# Power.net
KiCad netlist of a schematic drawn in Altium Designer
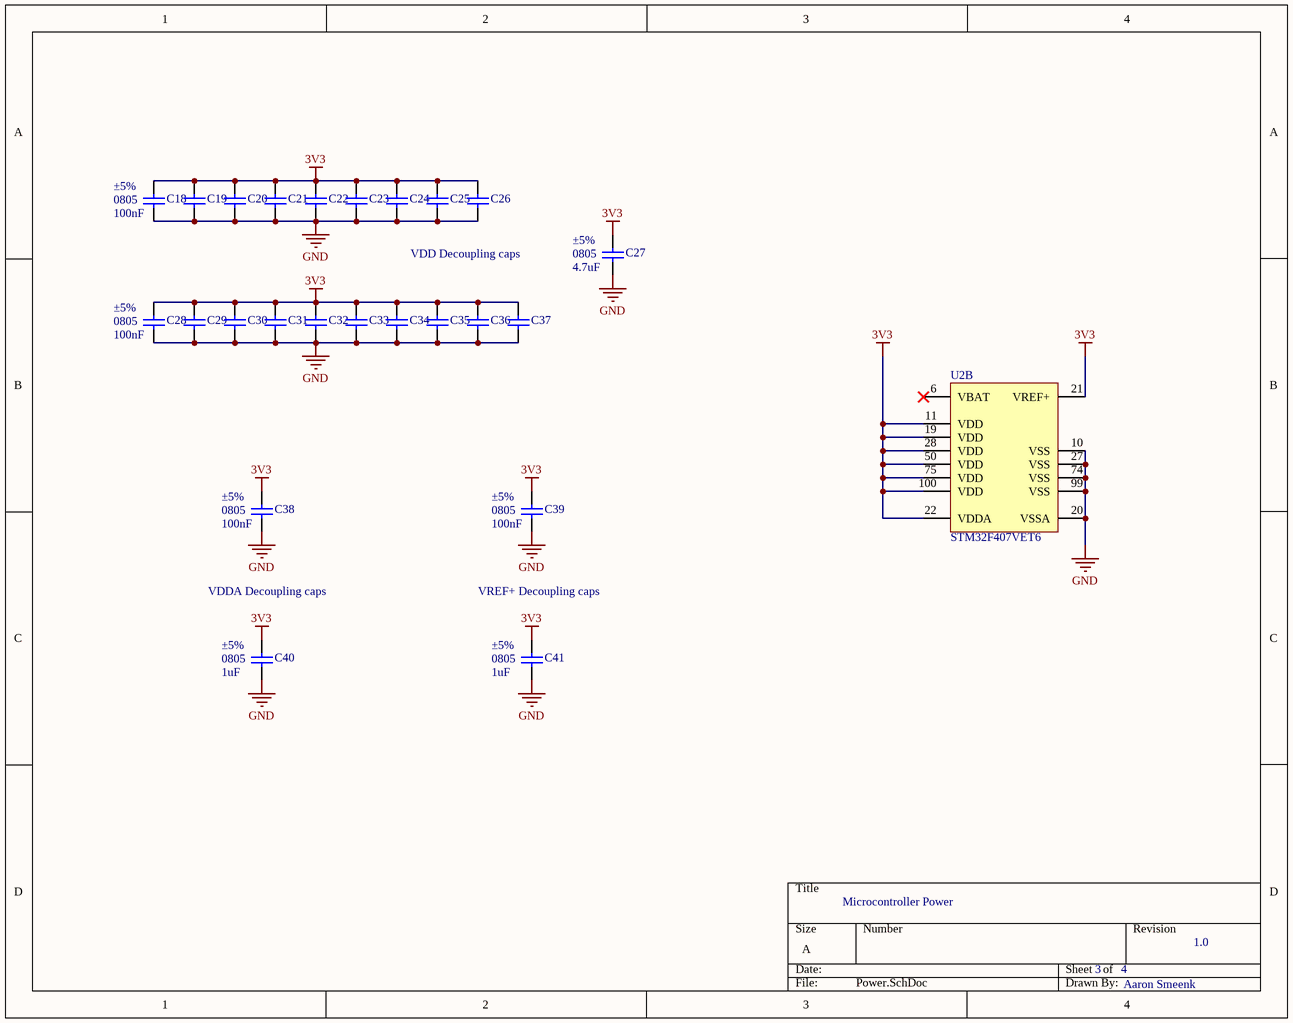
[diagram p0: Power.SchDoc]

(export (version "E")
  (design (tool "Eeschema 10.0.6"))
  (components
    (comp (ref "C18")
      (value "100nF")
      (footprint "CAPC0805(2012)100_M")
      (description "CAP 100nF 6.3V ±5% 0805 (2012 Metric) Thickness 1mm SMD")
      (fields
        (field (name "TOLERANCE") "±5%")
        (field (name "CASE-EIA") "0805")
        (field (name "Comment") "CAP 100nF 6.3V 0805(2012)")
      )
      (libsource (lib "Altium Content Vault") (part "CMP-1036-04390-1"))
    )
    (comp (ref "C19")
      (value "CAP 100nF 6.3V 0805(2012)")
      (footprint "CAPC0805(2012)100_M")
      (description "CAP 100nF 6.3V ±5% 0805 (2012 Metric) Thickness 1mm SMD")
      (fields (field (name "TOLERANCE") "±5%"))
      (libsource (lib "Altium Content Vault") (part "CMP-1036-04390-1"))
    )
    (comp (ref "C20")
      (value "CAP 100nF 6.3V 0805(2012)")
      (footprint "CAPC0805(2012)100_M")
      (description "CAP 100nF 6.3V ±5% 0805 (2012 Metric) Thickness 1mm SMD")
      (fields (field (name "TOLERANCE") "±5%"))
      (libsource (lib "Altium Content Vault") (part "CMP-1036-04390-1"))
    )
    (comp (ref "C21")
      (value "CAP 100nF 6.3V 0805(2012)")
      (footprint "CAPC0805(2012)100_M")
      (description "CAP 100nF 6.3V ±5% 0805 (2012 Metric) Thickness 1mm SMD")
      (fields (field (name "TOLERANCE") "±5%"))
      (libsource (lib "Altium Content Vault") (part "CMP-1036-04390-1"))
    )
    (comp (ref "C22")
      (value "CAP 100nF 6.3V 0805(2012)")
      (footprint "CAPC0805(2012)100_M")
      (description "CAP 100nF 6.3V ±5% 0805 (2012 Metric) Thickness 1mm SMD")
      (fields (field (name "TOLERANCE") "±5%"))
      (libsource (lib "Altium Content Vault") (part "CMP-1036-04390-1"))
    )
    (comp (ref "C23")
      (value "CAP 100nF 6.3V 0805(2012)")
      (footprint "CAPC0805(2012)100_M")
      (description "CAP 100nF 6.3V ±5% 0805 (2012 Metric) Thickness 1mm SMD")
      (fields (field (name "TOLERANCE") "±5%"))
      (libsource (lib "Altium Content Vault") (part "CMP-1036-04390-1"))
    )
    (comp (ref "C24")
      (value "CAP 100nF 6.3V 0805(2012)")
      (footprint "CAPC0805(2012)100_M")
      (description "CAP 100nF 6.3V ±5% 0805 (2012 Metric) Thickness 1mm SMD")
      (fields (field (name "TOLERANCE") "±5%"))
      (libsource (lib "Altium Content Vault") (part "CMP-1036-04390-1"))
    )
    (comp (ref "C25")
      (value "CAP 100nF 6.3V 0805(2012)")
      (footprint "CAPC0805(2012)100_M")
      (description "CAP 100nF 6.3V ±5% 0805 (2012 Metric) Thickness 1mm SMD")
      (fields (field (name "TOLERANCE") "±5%"))
      (libsource (lib "Altium Content Vault") (part "CMP-1036-04390-1"))
    )
    (comp (ref "C26")
      (value "CAP 100nF 6.3V 0805(2012)")
      (footprint "CAPC0805(2012)100_M")
      (description "CAP 100nF 6.3V ±5% 0805 (2012 Metric) Thickness 1mm SMD")
      (fields (field (name "TOLERANCE") "±5%"))
      (libsource (lib "Altium Content Vault") (part "CMP-1036-04390-1"))
    )
    (comp (ref "C27")
      (value "4.7uF")
      (footprint "CAPC0805(2012)145_L")
      (description "CAP 4.7uF 6.3V ±5% 0805 (2012 Metric) Thickness 1.45mm SMD")
      (fields
        (field (name "CASE-EIA") "0805")
        (field (name "TOLERANCE") "±5%")
        (field (name "Comment") "CAP 4.7uF 6.3V 0805(2012)")
      )
      (libsource (lib "Altium Content Vault") (part "CMP-1036-04781-1"))
    )
    (comp (ref "C28")
      (value "100nF")
      (footprint "CAPC0805(2012)100_M")
      (description "CAP 100nF 6.3V ±5% 0805 (2012 Metric) Thickness 1mm SMD")
      (fields
        (field (name "TOLERANCE") "±5%")
        (field (name "CASE-EIA") "0805")
        (field (name "Comment") "CAP 100nF 6.3V 0805(2012)")
      )
      (libsource (lib "Altium Content Vault") (part "CMP-1036-04390-1"))
    )
    (comp (ref "C29")
      (value "CAP 100nF 6.3V 0805(2012)")
      (footprint "CAPC0805(2012)100_M")
      (description "CAP 100nF 6.3V ±5% 0805 (2012 Metric) Thickness 1mm SMD")
      (fields (field (name "TOLERANCE") "±5%"))
      (libsource (lib "Altium Content Vault") (part "CMP-1036-04390-1"))
    )
    (comp (ref "C30")
      (value "CAP 100nF 6.3V 0805(2012)")
      (footprint "CAPC0805(2012)100_M")
      (description "CAP 100nF 6.3V ±5% 0805 (2012 Metric) Thickness 1mm SMD")
      (fields (field (name "TOLERANCE") "±5%"))
      (libsource (lib "Altium Content Vault") (part "CMP-1036-04390-1"))
    )
    (comp (ref "C31")
      (value "CAP 100nF 6.3V 0805(2012)")
      (footprint "CAPC0805(2012)100_M")
      (description "CAP 100nF 6.3V ±5% 0805 (2012 Metric) Thickness 1mm SMD")
      (fields (field (name "TOLERANCE") "±5%"))
      (libsource (lib "Altium Content Vault") (part "CMP-1036-04390-1"))
    )
    (comp (ref "C32")
      (value "CAP 100nF 6.3V 0805(2012)")
      (footprint "CAPC0805(2012)100_M")
      (description "CAP 100nF 6.3V ±5% 0805 (2012 Metric) Thickness 1mm SMD")
      (fields (field (name "TOLERANCE") "±5%"))
      (libsource (lib "Altium Content Vault") (part "CMP-1036-04390-1"))
    )
    (comp (ref "C33")
      (value "CAP 100nF 6.3V 0805(2012)")
      (footprint "CAPC0805(2012)100_M")
      (description "CAP 100nF 6.3V ±5% 0805 (2012 Metric) Thickness 1mm SMD")
      (fields (field (name "TOLERANCE") "±5%"))
      (libsource (lib "Altium Content Vault") (part "CMP-1036-04390-1"))
    )
    (comp (ref "C34")
      (value "CAP 100nF 6.3V 0805(2012)")
      (footprint "CAPC0805(2012)100_M")
      (description "CAP 100nF 6.3V ±5% 0805 (2012 Metric) Thickness 1mm SMD")
      (fields (field (name "TOLERANCE") "±5%"))
      (libsource (lib "Altium Content Vault") (part "CMP-1036-04390-1"))
    )
    (comp (ref "C35")
      (value "CAP 100nF 6.3V 0805(2012)")
      (footprint "CAPC0805(2012)100_M")
      (description "CAP 100nF 6.3V ±5% 0805 (2012 Metric) Thickness 1mm SMD")
      (fields (field (name "TOLERANCE") "±5%"))
      (libsource (lib "Altium Content Vault") (part "CMP-1036-04390-1"))
    )
    (comp (ref "C36")
      (value "CAP 100nF 6.3V 0805(2012)")
      (footprint "CAPC0805(2012)100_M")
      (description "CAP 100nF 6.3V ±5% 0805 (2012 Metric) Thickness 1mm SMD")
      (fields (field (name "TOLERANCE") "±5%"))
      (libsource (lib "Altium Content Vault") (part "CMP-1036-04390-1"))
    )
    (comp (ref "C37")
      (value "CAP 100nF 6.3V 0805(2012)")
      (footprint "CAPC0805(2012)100_M")
      (description "CAP 100nF 6.3V ±5% 0805 (2012 Metric) Thickness 1mm SMD")
      (fields (field (name "TOLERANCE") "±5%"))
      (libsource (lib "Altium Content Vault") (part "CMP-1036-04390-1"))
    )
    (comp (ref "C38")
      (value "100nF")
      (footprint "CAPC0805(2012)100_M")
      (description "CAP 100nF 6.3V ±5% 0805 (2012 Metric) Thickness 1mm SMD")
      (fields
        (field (name "TOLERANCE") "±5%")
        (field (name "CASE-EIA") "0805")
        (field (name "Comment") "CAP 100nF 6.3V 0805(2012)")
      )
      (libsource (lib "Altium Content Vault") (part "CMP-1036-04390-1"))
    )
    (comp (ref "C39")
      (value "100nF")
      (footprint "CAPC0805(2012)100_M")
      (description "CAP 100nF 6.3V ±5% 0805 (2012 Metric) Thickness 1mm SMD")
      (fields
        (field (name "TOLERANCE") "±5%")
        (field (name "CASE-EIA") "0805")
        (field (name "Comment") "CAP 100nF 6.3V 0805(2012)")
      )
      (libsource (lib "Altium Content Vault") (part "CMP-1036-04390-1"))
    )
    (comp (ref "C40")
      (value "1uF")
      (footprint "CAPC0805(2012)145_L")
      (description "CAP 1uF 6.3V ±5% 0805 (2012 Metric) Thickness 1.45mm SMD")
      (fields
        (field (name "CASE-EIA") "0805")
        (field (name "TOLERANCE") "±5%")
        (field (name "Comment") "CAP 1uF 6.3V 0805(2012)")
      )
      (libsource (lib "Altium Content Vault") (part "CMP-1036-04781-1"))
    )
    (comp (ref "C41")
      (value "1uF")
      (footprint "CAPC0805(2012)145_L")
      (description "CAP 1uF 6.3V ±5% 0805 (2012 Metric) Thickness 1.45mm SMD")
      (fields
        (field (name "CASE-EIA") "0805")
        (field (name "TOLERANCE") "±5%")
        (field (name "Comment") "CAP 1uF 6.3V 0805(2012)")
      )
      (libsource (lib "Altium Content Vault") (part "CMP-1036-04781-1"))
    )
    (comp (ref "U2")
      (value "STM32F407VET6")
      (footprint "STM-LQFP100_M")
      (fields (field (name "MANUFACTURER") "STMicroelectronics"))
      (libsource (lib "Altium Content Vault") (part "MC-ARM-STM32F40X_41X-SQ100"))
    )
  )
  (nets
    (net (code "1") (name "3V3") (class "Default")
      (node (ref "C18") (pin "2") (pinfunction "2_2") (pintype "passive"))
      (node (ref "C19") (pin "2") (pinfunction "2_2") (pintype "passive"))
      (node (ref "C20") (pin "2") (pinfunction "2_2") (pintype "passive"))
      (node (ref "C21") (pin "2") (pinfunction "2_2") (pintype "passive"))
      (node (ref "C22") (pin "2") (pinfunction "2_2") (pintype "passive"))
      (node (ref "C23") (pin "2") (pinfunction "2_2") (pintype "passive"))
      (node (ref "C24") (pin "2") (pinfunction "2_2") (pintype "passive"))
      (node (ref "C25") (pin "2") (pinfunction "2_2") (pintype "passive"))
      (node (ref "C26") (pin "2") (pinfunction "2_2") (pintype "passive"))
      (node (ref "C27") (pin "2") (pinfunction "2_2") (pintype "passive"))
      (node (ref "C28") (pin "2") (pinfunction "2_2") (pintype "passive"))
      (node (ref "C29") (pin "2") (pinfunction "2_2") (pintype "passive"))
      (node (ref "C30") (pin "2") (pinfunction "2_2") (pintype "passive"))
      (node (ref "C31") (pin "2") (pinfunction "2_2") (pintype "passive"))
      (node (ref "C32") (pin "2") (pinfunction "2_2") (pintype "passive"))
      (node (ref "C33") (pin "2") (pinfunction "2_2") (pintype "passive"))
      (node (ref "C34") (pin "2") (pinfunction "2_2") (pintype "passive"))
      (node (ref "C35") (pin "2") (pinfunction "2_2") (pintype "passive"))
      (node (ref "C36") (pin "2") (pinfunction "2_2") (pintype "passive"))
      (node (ref "C37") (pin "2") (pinfunction "2_2") (pintype "passive"))
      (node (ref "C38") (pin "2") (pinfunction "2_2") (pintype "passive"))
      (node (ref "C39") (pin "2") (pinfunction "2_2") (pintype "passive"))
      (node (ref "C40") (pin "2") (pinfunction "2_2") (pintype "passive"))
      (node (ref "C41") (pin "2") (pinfunction "2_2") (pintype "passive"))
      (node (ref "U2") (pin "100") (pinfunction "VDD_100") (pintype "power_in"))
      (node (ref "U2") (pin "11") (pinfunction "VDD_11") (pintype "power_in"))
      (node (ref "U2") (pin "19") (pinfunction "VDD_19") (pintype "power_in"))
      (node (ref "U2") (pin "21") (pinfunction "VREF+_21") (pintype "power_in"))
      (node (ref "U2") (pin "22") (pinfunction "VDDA_22") (pintype "power_in"))
      (node (ref "U2") (pin "28") (pinfunction "VDD_28") (pintype "power_in"))
      (node (ref "U2") (pin "50") (pinfunction "VDD_50") (pintype "power_in"))
      (node (ref "U2") (pin "75") (pinfunction "VDD_75") (pintype "power_in"))
    )
    (net (code "2") (name "GND") (class "Default")
      (node (ref "C18") (pin "1") (pinfunction "1_1") (pintype "passive"))
      (node (ref "C19") (pin "1") (pinfunction "1_1") (pintype "passive"))
      (node (ref "C20") (pin "1") (pinfunction "1_1") (pintype "passive"))
      (node (ref "C21") (pin "1") (pinfunction "1_1") (pintype "passive"))
      (node (ref "C22") (pin "1") (pinfunction "1_1") (pintype "passive"))
      (node (ref "C23") (pin "1") (pinfunction "1_1") (pintype "passive"))
      (node (ref "C24") (pin "1") (pinfunction "1_1") (pintype "passive"))
      (node (ref "C25") (pin "1") (pinfunction "1_1") (pintype "passive"))
      (node (ref "C26") (pin "1") (pinfunction "1_1") (pintype "passive"))
      (node (ref "C27") (pin "1") (pinfunction "1_1") (pintype "passive"))
      (node (ref "C28") (pin "1") (pinfunction "1_1") (pintype "passive"))
      (node (ref "C29") (pin "1") (pinfunction "1_1") (pintype "passive"))
      (node (ref "C30") (pin "1") (pinfunction "1_1") (pintype "passive"))
      (node (ref "C31") (pin "1") (pinfunction "1_1") (pintype "passive"))
      (node (ref "C32") (pin "1") (pinfunction "1_1") (pintype "passive"))
      (node (ref "C33") (pin "1") (pinfunction "1_1") (pintype "passive"))
      (node (ref "C34") (pin "1") (pinfunction "1_1") (pintype "passive"))
      (node (ref "C35") (pin "1") (pinfunction "1_1") (pintype "passive"))
      (node (ref "C36") (pin "1") (pinfunction "1_1") (pintype "passive"))
      (node (ref "C37") (pin "1") (pinfunction "1_1") (pintype "passive"))
      (node (ref "C38") (pin "1") (pinfunction "1_1") (pintype "passive"))
      (node (ref "C39") (pin "1") (pinfunction "1_1") (pintype "passive"))
      (node (ref "C40") (pin "1") (pinfunction "1_1") (pintype "passive"))
      (node (ref "C41") (pin "1") (pinfunction "1_1") (pintype "passive"))
      (node (ref "U2") (pin "10") (pinfunction "VSS_10") (pintype "power_in"))
      (node (ref "U2") (pin "20") (pinfunction "VSSA_20") (pintype "power_in"))
      (node (ref "U2") (pin "27") (pinfunction "VSS_27") (pintype "power_in"))
      (node (ref "U2") (pin "74") (pinfunction "VSS_74") (pintype "power_in"))
      (node (ref "U2") (pin "99") (pinfunction "VSS_99") (pintype "power_in"))
    )
    (net (code "3") (name "unconnected-(U2B-VBAT-Pad6)") (class "Default")
      (node (ref "U2") (pin "6") (pinfunction "VBAT_6") (pintype "power_in+no_connect"))
    )
  )
)
